# AUTO_plat.net
KiCad netlist of a schematic drawn in EAGLE
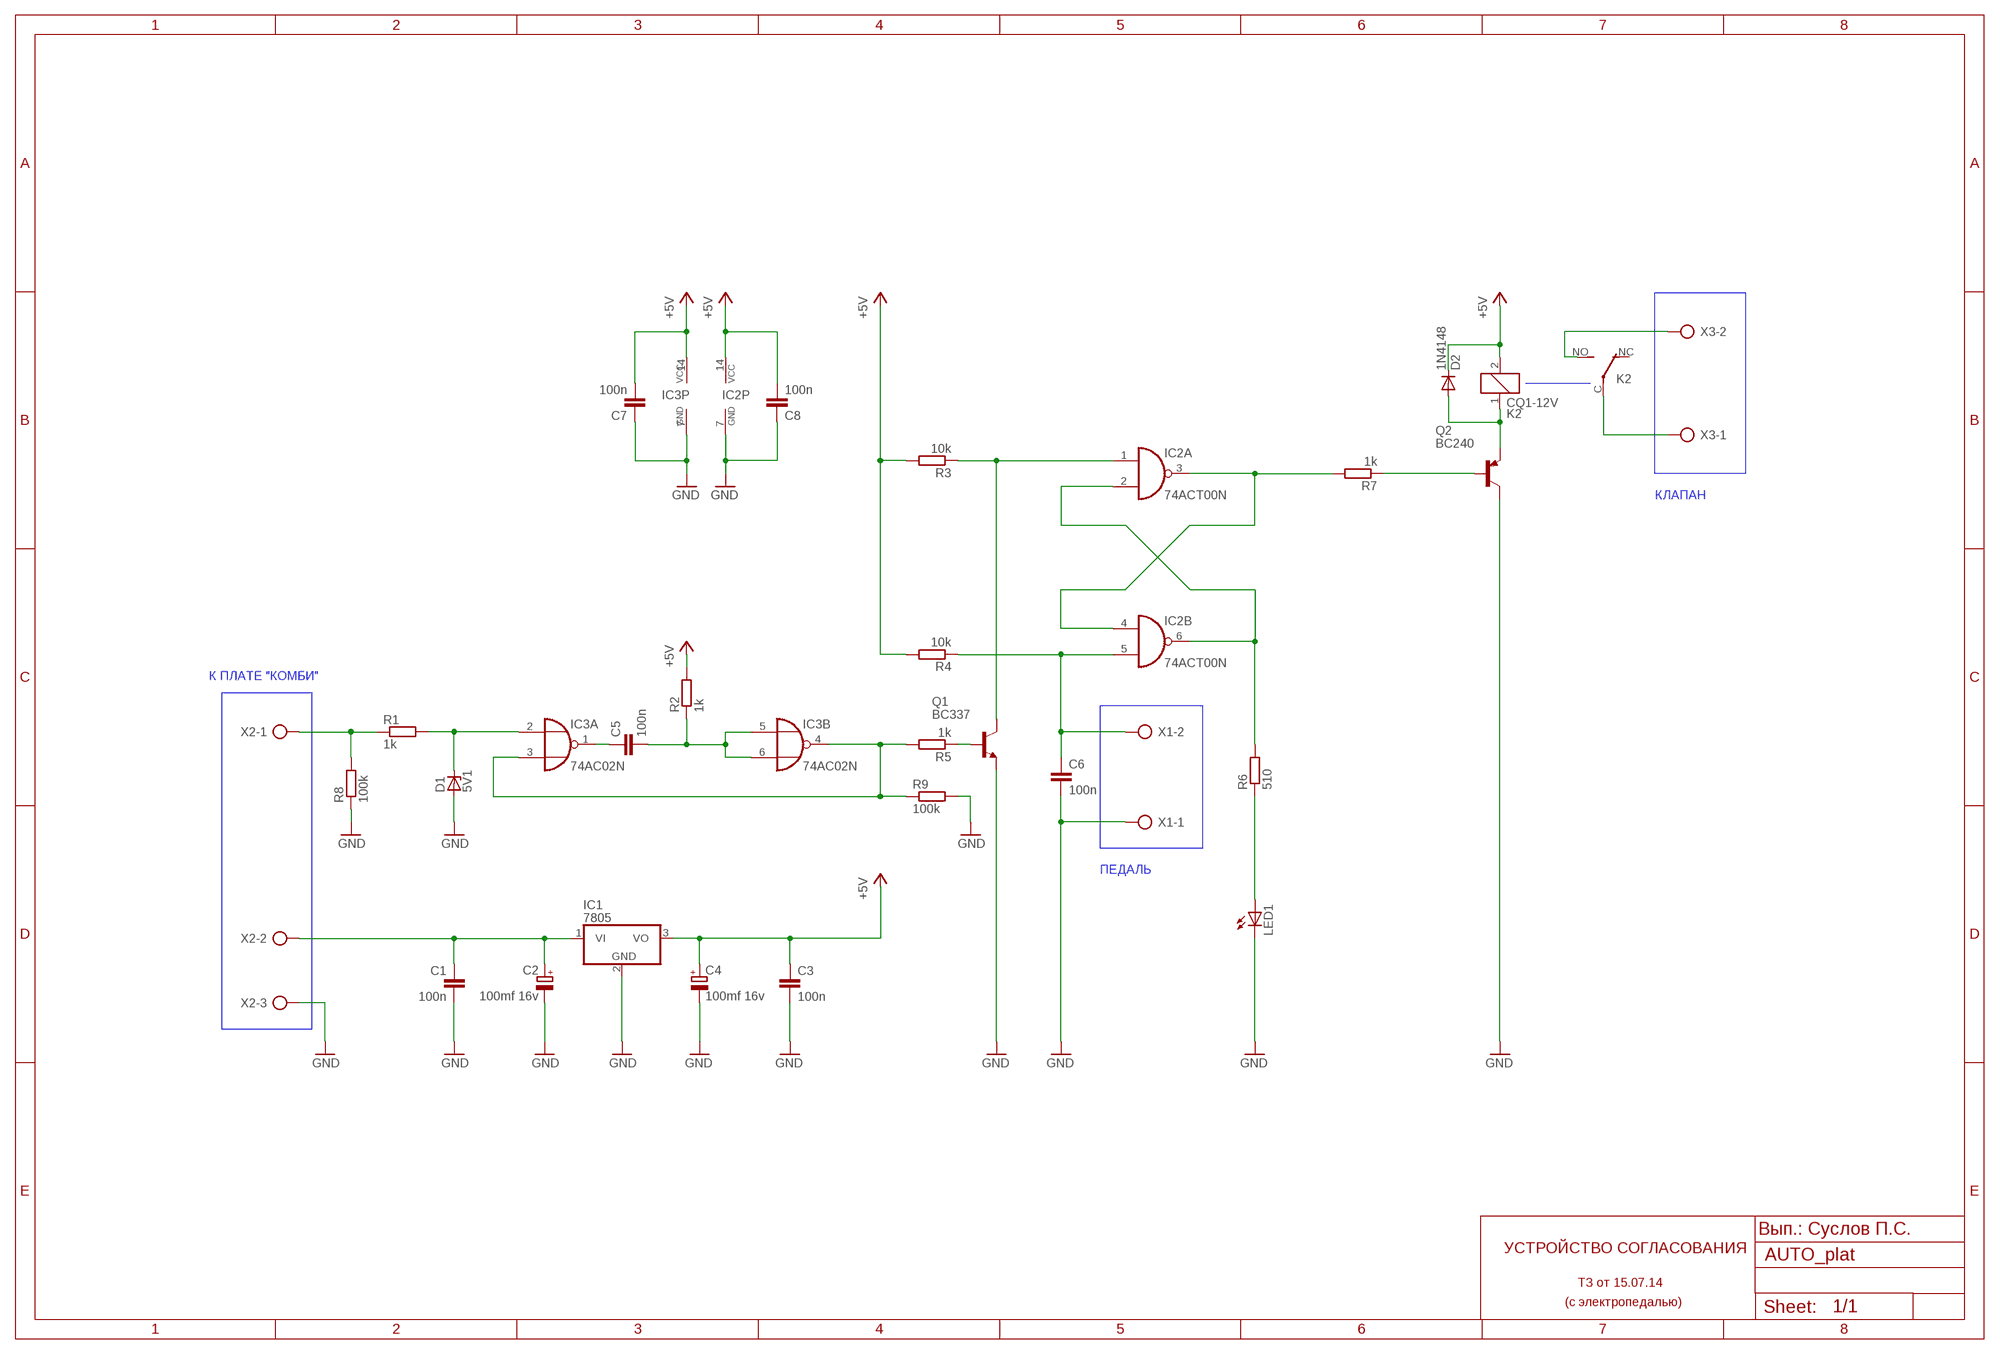
[diagram p0: schematic, sheet 1]

(export (version "E")
  (design (tool "Eeschema 10.0.6"))
  (components
    (comp (ref "C1")
      (value "100n")
      (footprint "eagle-import:C025-030X050")
      (libsource (lib "eagle-import") (part "C-EU025-030X050"))
    )
    (comp (ref "C2")
      (value "100mf 16v")
      (footprint "eagle-import:E3,5-8")
      (libsource (lib "eagle-import") (part "CPOL-EUE3.5-8"))
    )
    (comp (ref "C3")
      (value "100n")
      (footprint "eagle-import:C025-030X050")
      (libsource (lib "eagle-import") (part "C-EU025-030X050"))
    )
    (comp (ref "C4")
      (value "100mf 16v")
      (footprint "eagle-import:E3,5-8")
      (libsource (lib "eagle-import") (part "CPOL-EUE3.5-8"))
    )
    (comp (ref "C5")
      (value "100n")
      (footprint "eagle-import:C025-030X050")
      (libsource (lib "eagle-import") (part "C-EU025-030X050"))
    )
    (comp (ref "C6")
      (value "100n")
      (footprint "eagle-import:C025-030X050")
      (libsource (lib "eagle-import") (part "C-EU025-030X050"))
    )
    (comp (ref "C7")
      (value "100n")
      (footprint "eagle-import:C025-030X050")
      (libsource (lib "eagle-import") (part "C-EU025-030X050"))
    )
    (comp (ref "C8")
      (value "100n")
      (footprint "eagle-import:C025-030X050")
      (libsource (lib "eagle-import") (part "C-EU025-030X050"))
    )
    (comp (ref "D1")
      (value "5V1")
      (footprint "eagle-import:DO41Z10")
      (libsource (lib "eagle-import") (part "1N4728"))
    )
    (comp (ref "D2")
      (value "1N4148")
      (footprint "eagle-import:DO35-10")
      (libsource (lib "eagle-import") (part "1N4148DO35-10"))
    )
    (comp (ref "IC1")
      (value "7805")
      (footprint "eagle-import:TO220V")
      (libsource (lib "eagle-import") (part "78TV6"))
    )
    (comp (ref "IC2")
      (value "74ACT00N")
      (footprint "eagle-import:DIL14")
      (libsource (lib "eagle-import") (part "7400NACT"))
    )
    (comp (ref "IC3")
      (value "74AC02N")
      (footprint "eagle-import:DIL14")
      (libsource (lib "eagle-import") (part "7402NAC"))
    )
    (comp (ref "K2")
      (value "CQ1-12V")
      (footprint "eagle-import:CQ1")
      (libsource (lib "eagle-import") (part "CQ1-12V"))
    )
    (comp (ref "LED1")
      (value "LED3MM")
      (footprint "eagle-import:LED3MM")
      (libsource (lib "eagle-import") (part "LED3MM"))
    )
    (comp (ref "Q1")
      (value "BC337")
      (footprint "eagle-import:TO92")
      (libsource (lib "eagle-import") (part "BC337"))
    )
    (comp (ref "Q2")
      (value "BC240")
      (footprint "eagle-import:TO220")
      (libsource (lib "eagle-import") (part "BD240"))
    )
    (comp (ref "R1")
      (value "1k")
      (footprint "eagle-import:0207_10")
      (libsource (lib "eagle-import") (part "R-EU_0207/10"))
    )
    (comp (ref "R2")
      (value "1k")
      (footprint "eagle-import:0207_10")
      (libsource (lib "eagle-import") (part "R-EU_0207/10"))
    )
    (comp (ref "R3")
      (value "10k")
      (footprint "eagle-import:0207_10")
      (libsource (lib "eagle-import") (part "R-EU_0207/10"))
    )
    (comp (ref "R4")
      (value "10k")
      (footprint "eagle-import:0207_10")
      (libsource (lib "eagle-import") (part "R-EU_0207/10"))
    )
    (comp (ref "R5")
      (value "1k")
      (footprint "eagle-import:0207_10")
      (libsource (lib "eagle-import") (part "R-EU_0207/10"))
    )
    (comp (ref "R6")
      (value "510")
      (footprint "eagle-import:0207_10")
      (libsource (lib "eagle-import") (part "R-EU_0207/10"))
    )
    (comp (ref "R7")
      (value "1k")
      (footprint "eagle-import:0207_10")
      (libsource (lib "eagle-import") (part "R-EU_0207/10"))
    )
    (comp (ref "R8")
      (value "100k")
      (footprint "eagle-import:0207_10")
      (libsource (lib "eagle-import") (part "R-EU_0207/10"))
    )
    (comp (ref "R9")
      (value "100k")
      (footprint "eagle-import:0207_10")
      (libsource (lib "eagle-import") (part "R-EU_0207/10"))
    )
    (comp (ref "X1")
      (value "AK500/2")
      (footprint "eagle-import:AK500_2")
      (libsource (lib "eagle-import") (part "AK500/2"))
    )
    (comp (ref "X2")
      (value "AK500/3")
      (footprint "eagle-import:AK500_3")
      (libsource (lib "eagle-import") (part "AK500/3"))
    )
    (comp (ref "X3")
      (value "AK500/2")
      (footprint "eagle-import:AK500_2")
      (libsource (lib "eagle-import") (part "AK500/2"))
    )
  )
  (nets
    (net (code "1") (name "+5V") (class "Default")
      (node (ref "C3") (pin "1") (pinfunction "1_1") (pintype "passive"))
      (node (ref "C4") (pin "+") (pinfunction "+_+") (pintype "passive"))
      (node (ref "C7") (pin "2") (pinfunction "2_2") (pintype "passive"))
      (node (ref "C8") (pin "2") (pinfunction "2_2") (pintype "passive"))
      (node (ref "D2") (pin "C") (pinfunction "C_C") (pintype "passive"))
      (node (ref "IC1") (pin "3") (pinfunction "VO_3") (pintype "passive"))
      (node (ref "IC2") (pin "14") (pinfunction "VCC_14") (pintype "power_in"))
      (node (ref "IC3") (pin "14") (pinfunction "VCC_14") (pintype "power_in"))
      (node (ref "K2") (pin "2") (pinfunction "2_2") (pintype "passive"))
      (node (ref "R2") (pin "2") (pinfunction "2_2") (pintype "passive"))
      (node (ref "R3") (pin "2") (pinfunction "2_2") (pintype "passive"))
      (node (ref "R4") (pin "2") (pinfunction "2_2") (pintype "passive"))
    )
    (net (code "2") (name "GND") (class "Default")
      (node (ref "C1") (pin "2") (pinfunction "2_2") (pintype "passive"))
      (node (ref "C2") (pin "-") (pinfunction "-_-") (pintype "passive"))
      (node (ref "C3") (pin "2") (pinfunction "2_2") (pintype "passive"))
      (node (ref "C4") (pin "-") (pinfunction "-_-") (pintype "passive"))
      (node (ref "C6") (pin "2") (pinfunction "2_2") (pintype "passive"))
      (node (ref "C7") (pin "1") (pinfunction "1_1") (pintype "passive"))
      (node (ref "C8") (pin "1") (pinfunction "1_1") (pintype "passive"))
      (node (ref "D1") (pin "A") (pinfunction "A_A") (pintype "passive"))
      (node (ref "IC1") (pin "2") (pinfunction "GND_2") (pintype "passive"))
      (node (ref "IC2") (pin "7") (pinfunction "GND_7") (pintype "power_in"))
      (node (ref "IC3") (pin "7") (pinfunction "GND_7") (pintype "power_in"))
      (node (ref "LED1") (pin "K") (pinfunction "C_K") (pintype "passive"))
      (node (ref "Q1") (pin "1") (pinfunction "E_1") (pintype "passive"))
      (node (ref "Q2") (pin "2") (pinfunction "C_2") (pintype "passive"))
      (node (ref "R8") (pin "1") (pinfunction "1_1") (pintype "passive"))
      (node (ref "R9") (pin "2") (pinfunction "2_2") (pintype "passive"))
      (node (ref "X1") (pin "1") (pinfunction "KL_1") (pintype "passive"))
      (node (ref "X2") (pin "3") (pinfunction "KL_3") (pintype "passive"))
    )
    (net (code "3") (name "Net-(IC1-VI)") (class "Default")
      (node (ref "C1") (pin "1") (pinfunction "1_1") (pintype "passive"))
      (node (ref "C2") (pin "+") (pinfunction "+_+") (pintype "passive"))
      (node (ref "IC1") (pin "1") (pinfunction "VI_1") (pintype "input"))
      (node (ref "X2") (pin "2") (pinfunction "KL_2") (pintype "passive"))
    )
    (net (code "4") (name "Net-(IC2A-I0)") (class "Default")
      (node (ref "IC2") (pin "1") (pinfunction "I0_1") (pintype "input"))
      (node (ref "Q1") (pin "3") (pinfunction "C_3") (pintype "passive"))
      (node (ref "R3") (pin "1") (pinfunction "1_1") (pintype "passive"))
    )
    (net (code "5") (name "Net-(IC2A-I1)") (class "Default")
      (node (ref "IC2") (pin "2") (pinfunction "I1_2") (pintype "input"))
      (node (ref "IC2") (pin "6") (pinfunction "O_6") (pintype "output"))
      (node (ref "R6") (pin "2") (pinfunction "2_2") (pintype "passive"))
    )
    (net (code "6") (name "Net-(IC2A-O)") (class "Default")
      (node (ref "IC2") (pin "3") (pinfunction "O_3") (pintype "output"))
      (node (ref "IC2") (pin "4") (pinfunction "I0_4") (pintype "input"))
      (node (ref "R7") (pin "2") (pinfunction "2_2") (pintype "passive"))
    )
    (net (code "7") (name "Net-(IC2B-I1)") (class "Default")
      (node (ref "C6") (pin "1") (pinfunction "1_1") (pintype "passive"))
      (node (ref "IC2") (pin "5") (pinfunction "I1_5") (pintype "input"))
      (node (ref "R4") (pin "1") (pinfunction "1_1") (pintype "passive"))
      (node (ref "X1") (pin "2") (pinfunction "KL_2") (pintype "passive"))
    )
    (net (code "8") (name "Net-(IC3A-I0)") (class "Default")
      (node (ref "D1") (pin "C") (pinfunction "C_C") (pintype "passive"))
      (node (ref "IC3") (pin "2") (pinfunction "I0_2") (pintype "input"))
      (node (ref "R1") (pin "2") (pinfunction "2_2") (pintype "passive"))
    )
    (net (code "9") (name "Net-(IC3A-I1)") (class "Default")
      (node (ref "IC3") (pin "3") (pinfunction "I1_3") (pintype "input"))
      (node (ref "IC3") (pin "4") (pinfunction "O_4") (pintype "output"))
      (node (ref "R5") (pin "2") (pinfunction "2_2") (pintype "passive"))
      (node (ref "R9") (pin "1") (pinfunction "1_1") (pintype "passive"))
    )
    (net (code "10") (name "Net-(IC3A-O)") (class "Default")
      (node (ref "C5") (pin "1") (pinfunction "1_1") (pintype "passive"))
      (node (ref "IC3") (pin "1") (pinfunction "O_1") (pintype "output"))
    )
    (net (code "11") (name "Net-(IC3B-I0)") (class "Default")
      (node (ref "C5") (pin "2") (pinfunction "2_2") (pintype "passive"))
      (node (ref "IC3") (pin "5") (pinfunction "I0_5") (pintype "input"))
      (node (ref "IC3") (pin "6") (pinfunction "I1_6") (pintype "input"))
      (node (ref "R2") (pin "1") (pinfunction "1_1") (pintype "passive"))
    )
    (net (code "12") (name "Net-(K2B-P)") (class "Default")
      (node (ref "K2") (pin "C") (pinfunction "P_C") (pintype "passive"))
      (node (ref "X3") (pin "1") (pinfunction "KL_1") (pintype "passive"))
    )
    (net (code "13") (name "Net-(K2B-S)") (class "Default")
      (node (ref "K2") (pin "NO") (pinfunction "S_NO") (pintype "passive"))
      (node (ref "X3") (pin "2") (pinfunction "KL_2") (pintype "passive"))
    )
    (net (code "14") (name "Net-(LED1-PadA)") (class "Default")
      (node (ref "LED1") (pin "A") (pinfunction "A_A") (pintype "passive"))
      (node (ref "R6") (pin "1") (pinfunction "1_1") (pintype "passive"))
    )
    (net (code "15") (name "Net-(Q1-B)") (class "Default")
      (node (ref "Q1") (pin "2") (pinfunction "B_2") (pintype "passive"))
      (node (ref "R5") (pin "1") (pinfunction "1_1") (pintype "passive"))
    )
    (net (code "16") (name "Net-(Q2-B)") (class "Default")
      (node (ref "Q2") (pin "1") (pinfunction "B_1") (pintype "passive"))
      (node (ref "R7") (pin "1") (pinfunction "1_1") (pintype "passive"))
    )
    (net (code "17") (name "Net-(Q2-E)") (class "Default")
      (node (ref "D2") (pin "A") (pinfunction "A_A") (pintype "passive"))
      (node (ref "K2") (pin "1") (pinfunction "1_1") (pintype "passive"))
      (node (ref "Q2") (pin "3") (pinfunction "E_3") (pintype "passive"))
    )
    (net (code "18") (name "Net-(X2A-KL)") (class "Default")
      (node (ref "R1") (pin "1") (pinfunction "1_1") (pintype "passive"))
      (node (ref "R8") (pin "2") (pinfunction "2_2") (pintype "passive"))
      (node (ref "X2") (pin "1") (pinfunction "KL_1") (pintype "passive"))
    )
    (net (code "19") (name "unconnected-(K2B-O-PadNC)") (class "Default")
      (node (ref "K2") (pin "NC") (pinfunction "O_NC") (pintype "passive"))
    )
  )
)
